# GrooveStrip.net
KiCad netlist of a schematic drawn in EAGLE
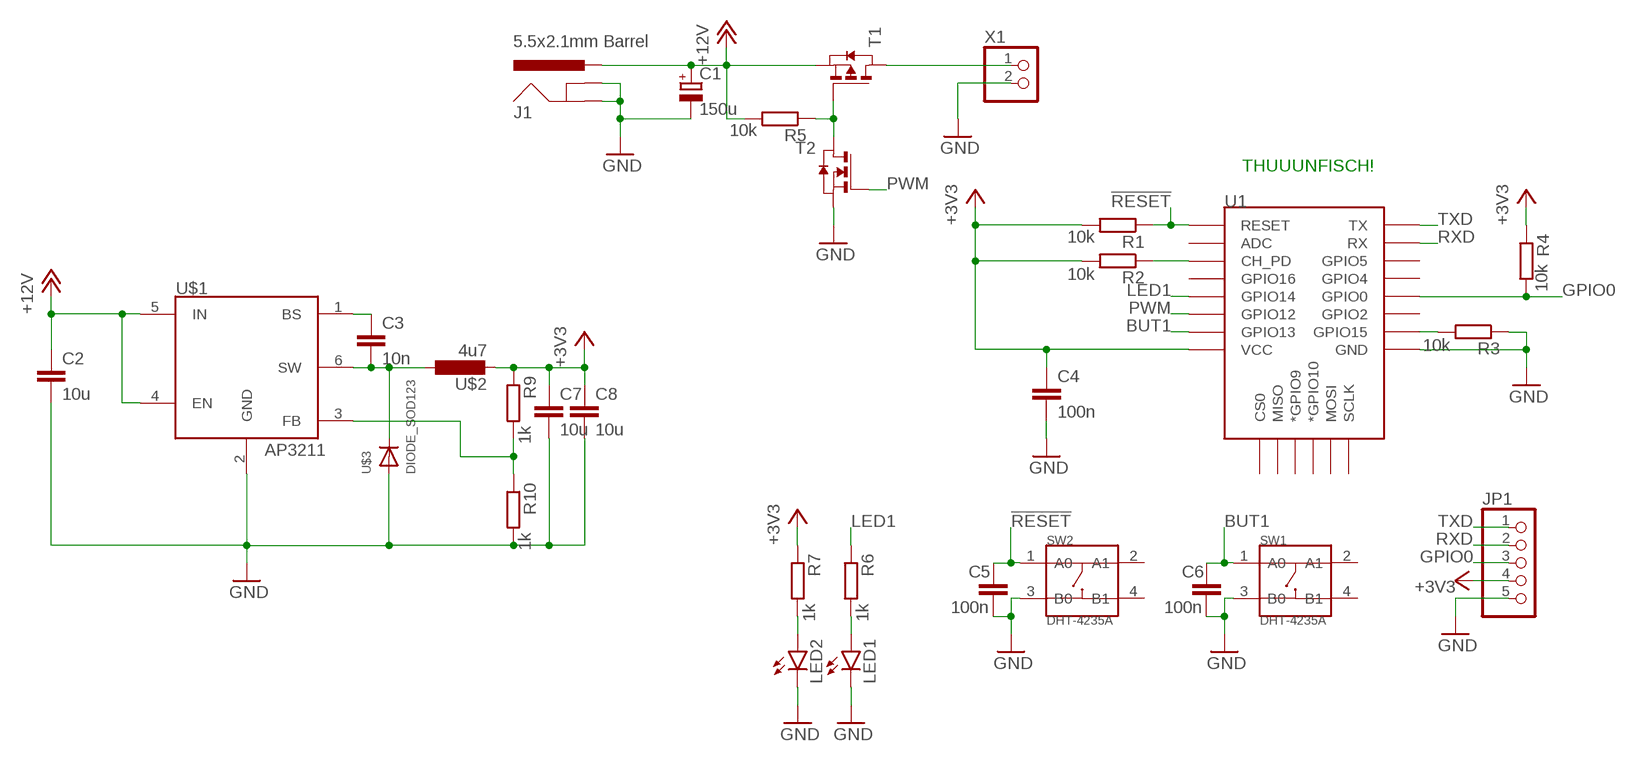
[diagram p0: schematic, sheet 1]

(export (version "E")
  (design (tool "Eeschema 10.0.6"))
  (components
    (comp (ref "C1")
      (value "150u")
      (footprint "eagle-import:PANASONIC_D")
      (libsource (lib "eagle-import") (part "CPOL-EUD"))
    )
    (comp (ref "C2")
      (value "10u")
      (footprint "eagle-import:C0805")
      (libsource (lib "eagle-import") (part "C-EUC0805"))
    )
    (comp (ref "C3")
      (value "10n")
      (footprint "eagle-import:C0805")
      (libsource (lib "eagle-import") (part "C-EUC0805"))
    )
    (comp (ref "C4")
      (value "100n")
      (footprint "eagle-import:C0805")
      (libsource (lib "eagle-import") (part "C-EUC0805"))
    )
    (comp (ref "C5")
      (value "100n")
      (footprint "eagle-import:C0805")
      (libsource (lib "eagle-import") (part "C-EUC0805"))
    )
    (comp (ref "C6")
      (value "100n")
      (footprint "eagle-import:C0805")
      (libsource (lib "eagle-import") (part "C-EUC0805"))
    )
    (comp (ref "C7")
      (value "10u")
      (footprint "eagle-import:C0805")
      (libsource (lib "eagle-import") (part "C-EUC0805"))
    )
    (comp (ref "C8")
      (value "10u")
      (footprint "eagle-import:C0805")
      (libsource (lib "eagle-import") (part "C-EUC0805"))
    )
    (comp (ref "J1")
      (value "5.5x2.1mm Barrel")
      (footprint "eagle-import:POWER_JACK_SMD")
      (libsource (lib "eagle-import") (part "POWER_JACKSMD"))
    )
    (comp (ref "JP1")
      (value "PINHD-1X5")
      (footprint "eagle-import:1X05")
      (libsource (lib "eagle-import") (part "PINHD-1X5"))
    )
    (comp (ref "LED1")
      (value "LEDCHIPLED_0805")
      (footprint "eagle-import:CHIPLED_0805")
      (libsource (lib "eagle-import") (part "LEDCHIPLED_0805"))
    )
    (comp (ref "LED2")
      (value "LEDCHIPLED_0805")
      (footprint "eagle-import:CHIPLED_0805")
      (libsource (lib "eagle-import") (part "LEDCHIPLED_0805"))
    )
    (comp (ref "R1")
      (value "10k")
      (footprint "eagle-import:R0805")
      (libsource (lib "eagle-import") (part "R-EU_R0805"))
    )
    (comp (ref "R2")
      (value "10k")
      (footprint "eagle-import:R0805")
      (libsource (lib "eagle-import") (part "R-EU_R0805"))
    )
    (comp (ref "R3")
      (value "10k")
      (footprint "eagle-import:R0805")
      (libsource (lib "eagle-import") (part "R-EU_R0805"))
    )
    (comp (ref "R4")
      (value "10k")
      (footprint "eagle-import:R0805")
      (libsource (lib "eagle-import") (part "R-EU_R0805"))
    )
    (comp (ref "R5")
      (value "10k")
      (footprint "eagle-import:R0805")
      (libsource (lib "eagle-import") (part "R-EU_R0805"))
    )
    (comp (ref "R6")
      (value "1k")
      (footprint "eagle-import:R0805")
      (libsource (lib "eagle-import") (part "R-EU_R0805"))
    )
    (comp (ref "R7")
      (value "1k")
      (footprint "eagle-import:R0805")
      (libsource (lib "eagle-import") (part "R-EU_R0805"))
    )
    (comp (ref "R9")
      (value "1k")
      (footprint "eagle-import:R0805")
      (libsource (lib "eagle-import") (part "R-EU_R0805"))
    )
    (comp (ref "R10")
      (value "1k")
      (footprint "eagle-import:R0805")
      (libsource (lib "eagle-import") (part "R-EU_R0805"))
    )
    (comp (ref "SW1")
      (value "DHT-4235A")
      (footprint "eagle-import:SW4-SMD-4.2X3.2X2.5MM")
      (libsource (lib "eagle-import") (part "SMD-BUTTON-TOP-DHT-4235A(4P-4.2X3.2MM)"))
    )
    (comp (ref "SW2")
      (value "DHT-4235A")
      (footprint "eagle-import:SW4-SMD-4.2X3.2X2.5MM")
      (libsource (lib "eagle-import") (part "SMD-BUTTON-TOP-DHT-4235A(4P-4.2X3.2MM)"))
    )
    (comp (ref "T1")
      (value "PMOSSOT23")
      (footprint "eagle-import:SOT23-3")
      (libsource (lib "eagle-import") (part "PMOSSOT23"))
    )
    (comp (ref "T2")
      (value "NMOSSOT23")
      (footprint "eagle-import:SOT23-3")
      (libsource (lib "eagle-import") (part "NMOSSOT23"))
    )
    (comp (ref "U$1")
      (value "AP3211")
      (footprint "eagle-import:SOT23-6")
      (libsource (lib "eagle-import") (part "AP3211"))
    )
    (comp (ref "U$2")
      (value "4u7")
      (footprint "eagle-import:SRN5020")
      (libsource (lib "eagle-import") (part "SRN5020"))
    )
    (comp (ref "U$3")
      (value "DIODE_SOD123")
      (footprint "eagle-import:SOD-123")
      (libsource (lib "eagle-import") (part "DIODE_SOD123"))
    )
    (comp (ref "U1")
      (value "ESP12ESMD")
      (footprint "eagle-import:ESP12E-SMD")
      (libsource (lib "eagle-import") (part "ESP12ESMD"))
    )
    (comp (ref "X1")
      (value "W237-102")
      (footprint "eagle-import:SCREW_2P")
      (fields (field (name "MPN") "237-102"))
      (libsource (lib "eagle-import") (part "W237-102"))
    )
  )
  (nets
    (net (code "1") (name "+3V3") (class "Default")
      (node (ref "C4") (pin "1") (pinfunction "1_1") (pintype "passive"))
      (node (ref "C7") (pin "1") (pinfunction "1_1") (pintype "passive"))
      (node (ref "C8") (pin "1") (pinfunction "1_1") (pintype "passive"))
      (node (ref "JP1") (pin "4") (pinfunction "4_4") (pintype "passive"))
      (node (ref "R1") (pin "2") (pinfunction "2_2") (pintype "passive"))
      (node (ref "R2") (pin "2") (pinfunction "2_2") (pintype "passive"))
      (node (ref "R4") (pin "1") (pinfunction "1_1") (pintype "passive"))
      (node (ref "R7") (pin "1") (pinfunction "1_1") (pintype "passive"))
      (node (ref "R9") (pin "1") (pinfunction "1_1") (pintype "passive"))
      (node (ref "U$2") (pin "P$2") (pinfunction "2_P$2") (pintype "passive"))
      (node (ref "U1") (pin "VCC") (pinfunction "VCC_VCC") (pintype "bidirectional"))
    )
    (net (code "2") (name "+12V") (class "Default")
      (node (ref "C1") (pin "+") (pinfunction "+_+") (pintype "passive"))
      (node (ref "C2") (pin "1") (pinfunction "1_1") (pintype "passive"))
      (node (ref "J1") (pin "VIN0") (pinfunction "PWR_VIN0") (pintype "bidirectional"))
      (node (ref "R5") (pin "2") (pinfunction "2_2") (pintype "passive"))
      (node (ref "T1") (pin "2") (pinfunction "S_2") (pintype "passive"))
      (node (ref "U$1") (pin "4") (pinfunction "EN_4") (pintype "bidirectional"))
      (node (ref "U$1") (pin "5") (pinfunction "IN_5") (pintype "bidirectional"))
    )
    (net (code "3") (name "/BUT1") (class "Default")
      (node (ref "C6") (pin "1") (pinfunction "1_1") (pintype "passive"))
      (node (ref "SW1") (pin "1") (pinfunction "A0_1") (pintype "bidirectional"))
      (node (ref "U1") (pin "GPIO13") (pinfunction "GPIO13_GPIO13") (pintype "bidirectional"))
    )
    (net (code "4") (name "/GPIO0") (class "Default")
      (node (ref "JP1") (pin "3") (pinfunction "3_3") (pintype "passive"))
      (node (ref "R4") (pin "2") (pinfunction "2_2") (pintype "passive"))
      (node (ref "U1") (pin "GPIO0") (pinfunction "GPIO0_GPIO0") (pintype "bidirectional"))
    )
    (net (code "5") (name "/LED1") (class "Default")
      (node (ref "R6") (pin "1") (pinfunction "1_1") (pintype "passive"))
      (node (ref "U1") (pin "GPIO14") (pinfunction "GPIO14_GPIO14") (pintype "bidirectional"))
    )
    (net (code "6") (name "/PWM") (class "Default")
      (node (ref "T2") (pin "3") (pinfunction "G_3") (pintype "passive"))
      (node (ref "U1") (pin "GPIO12") (pinfunction "GPIO12_GPIO12") (pintype "bidirectional"))
    )
    (net (code "7") (name "/RXD") (class "Default")
      (node (ref "JP1") (pin "2") (pinfunction "2_2") (pintype "passive"))
      (node (ref "U1") (pin "RXD0") (pinfunction "RX_RXD0") (pintype "bidirectional"))
    )
    (net (code "8") (name "/TXD") (class "Default")
      (node (ref "JP1") (pin "1") (pinfunction "1_1") (pintype "passive"))
      (node (ref "U1") (pin "TXD0") (pinfunction "TX_TXD0") (pintype "bidirectional"))
    )
    (net (code "9") (name "/~{RESET}") (class "Default")
      (node (ref "C5") (pin "1") (pinfunction "1_1") (pintype "passive"))
      (node (ref "R1") (pin "1") (pinfunction "1_1") (pintype "passive"))
      (node (ref "SW2") (pin "1") (pinfunction "A0_1") (pintype "bidirectional"))
      (node (ref "U1") (pin "RESET") (pinfunction "RESET_RESET") (pintype "bidirectional"))
    )
    (net (code "10") (name "GND") (class "Default")
      (node (ref "C1") (pin "-") (pinfunction "-_-") (pintype "passive"))
      (node (ref "C2") (pin "2") (pinfunction "2_2") (pintype "passive"))
      (node (ref "C4") (pin "2") (pinfunction "2_2") (pintype "passive"))
      (node (ref "C5") (pin "2") (pinfunction "2_2") (pintype "passive"))
      (node (ref "C6") (pin "2") (pinfunction "2_2") (pintype "passive"))
      (node (ref "C7") (pin "2") (pinfunction "2_2") (pintype "passive"))
      (node (ref "C8") (pin "2") (pinfunction "2_2") (pintype "passive"))
      (node (ref "J1") (pin "GND") (pinfunction "GNDBREAK_GND") (pintype "bidirectional"))
      (node (ref "J1") (pin "P$4") (pinfunction "GND_P$4") (pintype "bidirectional"))
      (node (ref "JP1") (pin "5") (pinfunction "5_5") (pintype "passive"))
      (node (ref "LED1") (pin "C") (pinfunction "C_C") (pintype "passive"))
      (node (ref "LED2") (pin "C") (pinfunction "C_C") (pintype "passive"))
      (node (ref "R10") (pin "2") (pinfunction "2_2") (pintype "passive"))
      (node (ref "R3") (pin "1") (pinfunction "1_1") (pintype "passive"))
      (node (ref "SW1") (pin "3") (pinfunction "B0_3") (pintype "bidirectional"))
      (node (ref "SW2") (pin "3") (pinfunction "B0_3") (pintype "bidirectional"))
      (node (ref "T2") (pin "2") (pinfunction "S_2") (pintype "passive"))
      (node (ref "U$1") (pin "2") (pinfunction "GND_2") (pintype "bidirectional"))
      (node (ref "U$3") (pin "A") (pinfunction "A_A") (pintype "passive"))
      (node (ref "U1") (pin "GND") (pinfunction "GND_GND") (pintype "bidirectional"))
      (node (ref "X1") (pin "2") (pinfunction "2_2") (pintype "passive"))
    )
    (net (code "11") (name "Net-(LED1-PadA)") (class "Default")
      (node (ref "LED1") (pin "A") (pinfunction "A_A") (pintype "passive"))
      (node (ref "R6") (pin "2") (pinfunction "2_2") (pintype "passive"))
    )
    (net (code "12") (name "Net-(LED2-PadA)") (class "Default")
      (node (ref "LED2") (pin "A") (pinfunction "A_A") (pintype "passive"))
      (node (ref "R7") (pin "2") (pinfunction "2_2") (pintype "passive"))
    )
    (net (code "13") (name "Net-(R2-Pad1)") (class "Default")
      (node (ref "R2") (pin "1") (pinfunction "1_1") (pintype "passive"))
      (node (ref "U1") (pin "CH_PD") (pinfunction "CH_PD_CH_PD") (pintype "bidirectional"))
    )
    (net (code "14") (name "Net-(R3-Pad2)") (class "Default")
      (node (ref "R3") (pin "2") (pinfunction "2_2") (pintype "passive"))
      (node (ref "U1") (pin "GPIO15") (pinfunction "GPIO15_GPIO15") (pintype "bidirectional"))
    )
    (net (code "15") (name "Net-(T1-D)") (class "Default")
      (node (ref "T1") (pin "1") (pinfunction "D_1") (pintype "passive"))
      (node (ref "X1") (pin "1") (pinfunction "1_1") (pintype "passive"))
    )
    (net (code "16") (name "Net-(T1-G)") (class "Default")
      (node (ref "R5") (pin "1") (pinfunction "1_1") (pintype "passive"))
      (node (ref "T1") (pin "3") (pinfunction "G_3") (pintype "passive"))
      (node (ref "T2") (pin "1") (pinfunction "D_1") (pintype "passive"))
    )
    (net (code "17") (name "Net-(U$1-BS)") (class "Default")
      (node (ref "C3") (pin "1") (pinfunction "1_1") (pintype "passive"))
      (node (ref "U$1") (pin "1") (pinfunction "BS_1") (pintype "bidirectional"))
    )
    (net (code "18") (name "Net-(U$1-FB)") (class "Default")
      (node (ref "R10") (pin "1") (pinfunction "1_1") (pintype "passive"))
      (node (ref "R9") (pin "2") (pinfunction "2_2") (pintype "passive"))
      (node (ref "U$1") (pin "3") (pinfunction "FB_3") (pintype "bidirectional"))
    )
    (net (code "19") (name "Net-(U$1-SW)") (class "Default")
      (node (ref "C3") (pin "2") (pinfunction "2_2") (pintype "passive"))
      (node (ref "U$1") (pin "6") (pinfunction "SW_6") (pintype "bidirectional"))
      (node (ref "U$2") (pin "P$1") (pinfunction "1_P$1") (pintype "passive"))
      (node (ref "U$3") (pin "C") (pinfunction "C_C") (pintype "passive"))
    )
    (net (code "20") (name "unconnected-(SW1-A1-Pad2)") (class "Default")
      (node (ref "SW1") (pin "2") (pinfunction "A1_2") (pintype "bidirectional"))
    )
    (net (code "21") (name "unconnected-(SW1-B1-Pad4)") (class "Default")
      (node (ref "SW1") (pin "4") (pinfunction "B1_4") (pintype "bidirectional"))
    )
    (net (code "22") (name "unconnected-(SW2-A1-Pad2)") (class "Default")
      (node (ref "SW2") (pin "2") (pinfunction "A1_2") (pintype "bidirectional"))
    )
    (net (code "23") (name "unconnected-(SW2-B1-Pad4)") (class "Default")
      (node (ref "SW2") (pin "4") (pinfunction "B1_4") (pintype "bidirectional"))
    )
    (net (code "24") (name "unconnected-(U1-*GPIO9-PadGPIO9)") (class "Default")
      (node (ref "U1") (pin "GPIO9") (pinfunction "*GPIO9_GPIO9") (pintype "bidirectional"))
    )
    (net (code "25") (name "unconnected-(U1-*GPIO10-PadGPIO10)") (class "Default")
      (node (ref "U1") (pin "GPIO10") (pinfunction "*GPIO10_GPIO10") (pintype "bidirectional"))
    )
    (net (code "26") (name "unconnected-(U1-PadADC)") (class "Default")
      (node (ref "U1") (pin "ADC") (pinfunction "ADC_ADC") (pintype "bidirectional"))
    )
    (net (code "27") (name "unconnected-(U1-PadCS0)") (class "Default")
      (node (ref "U1") (pin "CS0") (pinfunction "CS0_CS0") (pintype "bidirectional"))
    )
    (net (code "28") (name "unconnected-(U1-PadGPIO2)") (class "Default")
      (node (ref "U1") (pin "GPIO2") (pinfunction "GPIO2_GPIO2") (pintype "bidirectional"))
    )
    (net (code "29") (name "unconnected-(U1-PadGPIO4)") (class "Default")
      (node (ref "U1") (pin "GPIO4") (pinfunction "GPIO4_GPIO4") (pintype "bidirectional"))
    )
    (net (code "30") (name "unconnected-(U1-PadGPIO5)") (class "Default")
      (node (ref "U1") (pin "GPIO5") (pinfunction "GPIO5_GPIO5") (pintype "bidirectional"))
    )
    (net (code "31") (name "unconnected-(U1-PadGPIO16)") (class "Default")
      (node (ref "U1") (pin "GPIO16") (pinfunction "GPIO16_GPIO16") (pintype "bidirectional"))
    )
    (net (code "32") (name "unconnected-(U1-PadMISO)") (class "Default")
      (node (ref "U1") (pin "MISO") (pinfunction "MISO_MISO") (pintype "bidirectional"))
    )
    (net (code "33") (name "unconnected-(U1-PadMOSI)") (class "Default")
      (node (ref "U1") (pin "MOSI") (pinfunction "MOSI_MOSI") (pintype "bidirectional"))
    )
    (net (code "34") (name "unconnected-(U1-PadSCLK)") (class "Default")
      (node (ref "U1") (pin "SCLK") (pinfunction "SCLK_SCLK") (pintype "bidirectional"))
    )
  )
)
